# CoPro.net
KiCad netlist of a schematic drawn in EAGLE
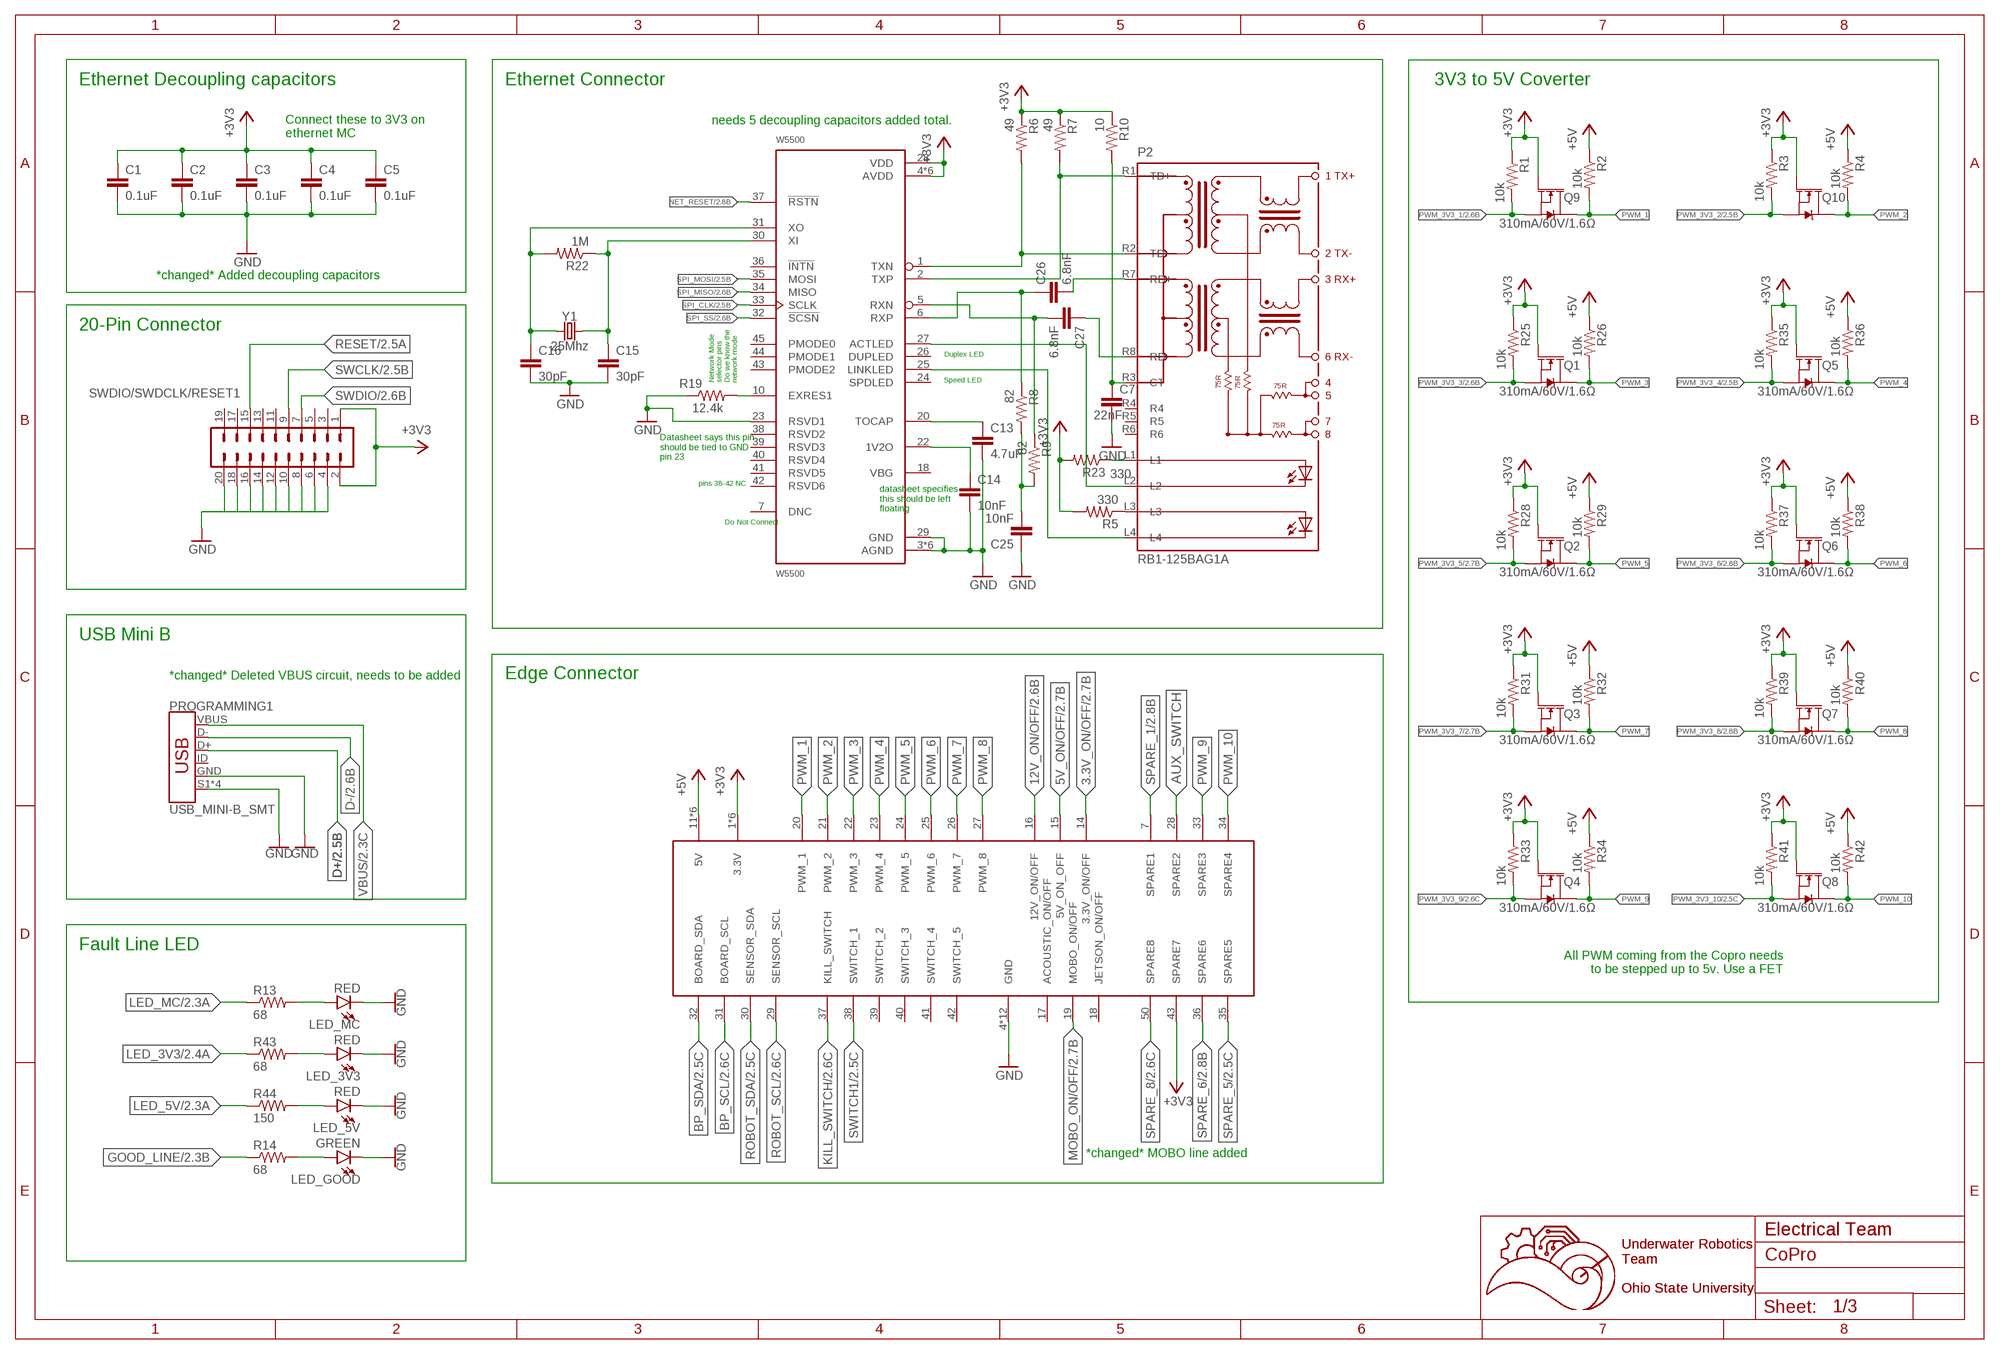
[diagram p0: schematic, sheet 1]
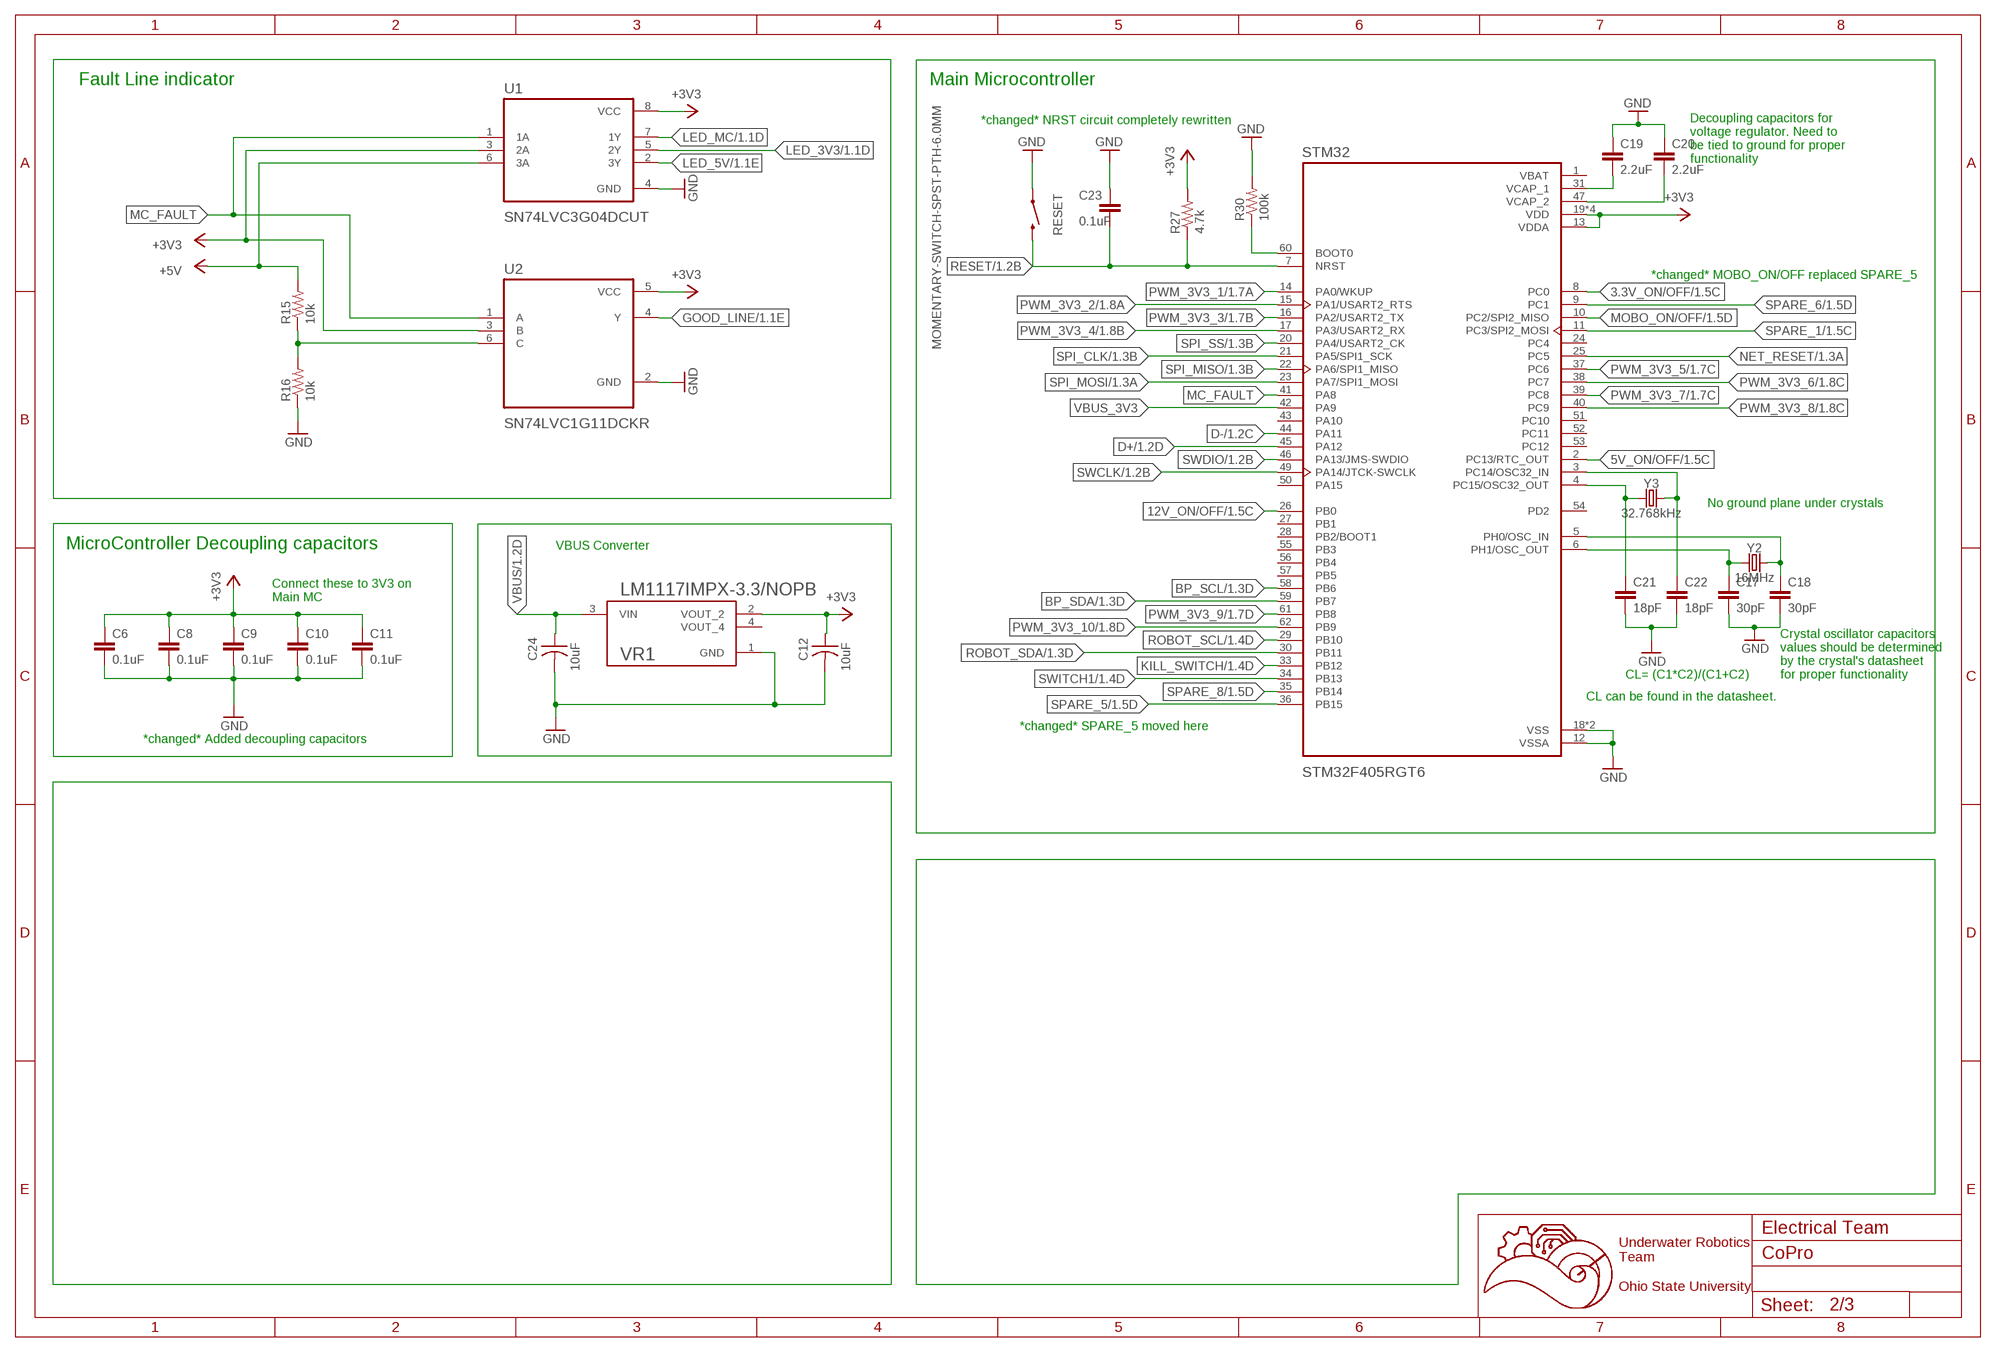
[diagram p1: schematic, sheet 2]
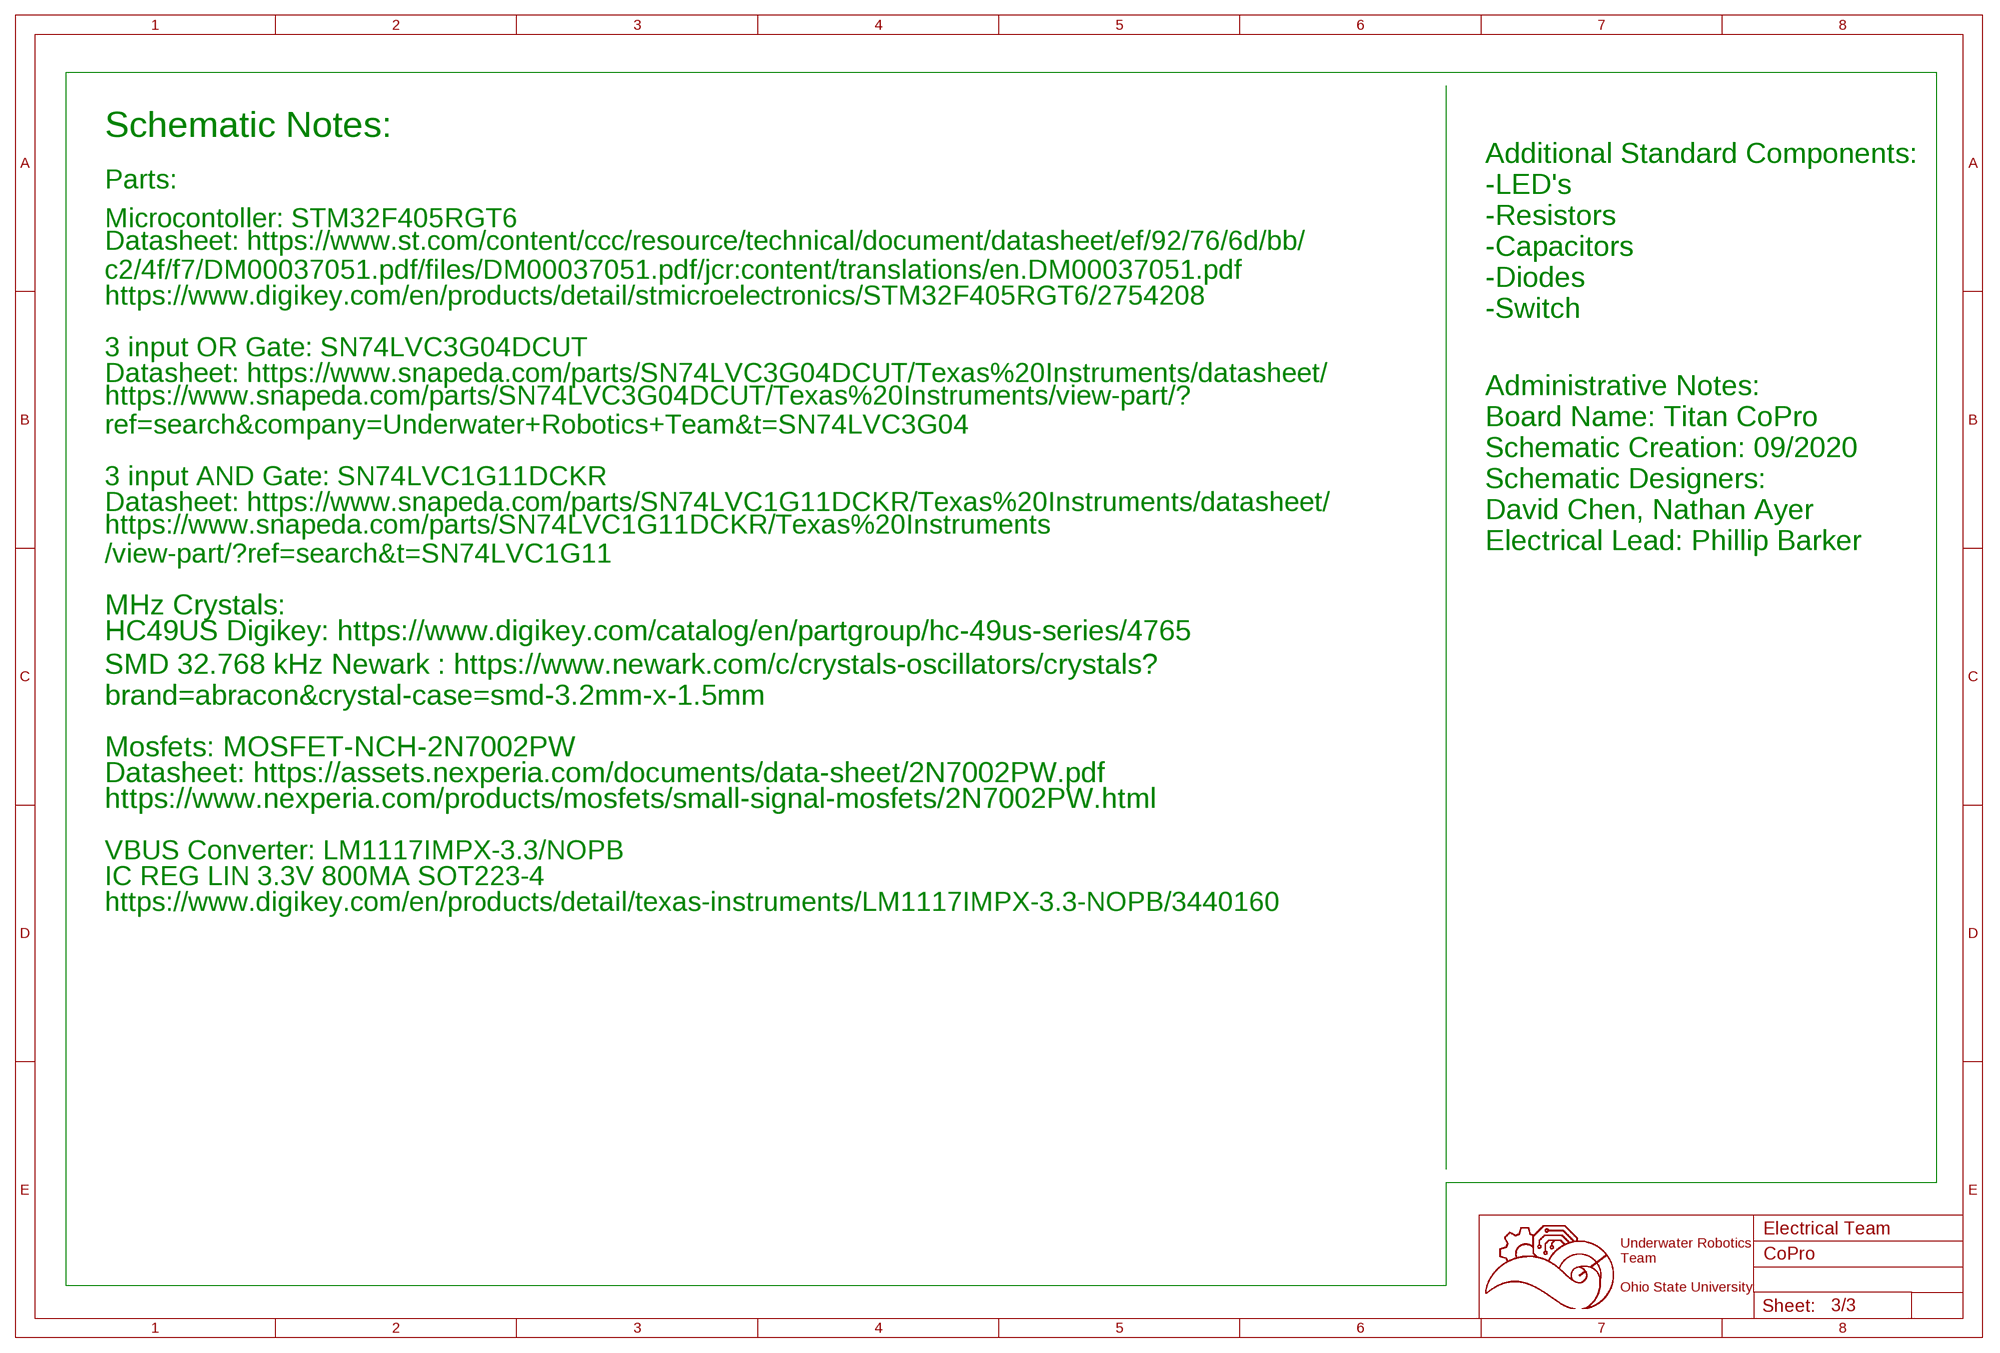
[diagram p2: schematic, sheet 3]

(export (version "E")
  (design (tool "Eeschema 10.0.6"))
  (components
    (comp (ref "C6")
      (value "0.1uF")
      (footprint "eagle-import:C0603")
      (libsource (lib "eagle-import") (part "C-EUC0603"))
    )
    (comp (ref "C8")
      (value "0.1uF")
      (footprint "eagle-import:C0603")
      (libsource (lib "eagle-import") (part "C-EUC0603"))
    )
    (comp (ref "C9")
      (value "0.1uF")
      (footprint "eagle-import:C0603")
      (libsource (lib "eagle-import") (part "C-EUC0603"))
    )
    (comp (ref "C10")
      (value "0.1uF")
      (footprint "eagle-import:C0603")
      (libsource (lib "eagle-import") (part "C-EUC0603"))
    )
    (comp (ref "C11")
      (value "0.1uF")
      (footprint "eagle-import:C0603")
      (libsource (lib "eagle-import") (part "C-EUC0603"))
    )
    (comp (ref "C12")
      (value "10uF")
      (footprint "eagle-import:C0603")
      (libsource (lib "eagle-import") (part "C-USC0603"))
    )
    (comp (ref "C17")
      (value "30pF")
      (footprint "eagle-import:C0603")
      (libsource (lib "eagle-import") (part "C-EUC0603"))
    )
    (comp (ref "C18")
      (value "30pF")
      (footprint "eagle-import:C0603")
      (libsource (lib "eagle-import") (part "C-EUC0603"))
    )
    (comp (ref "C19")
      (value "2.2uF")
      (footprint "eagle-import:C0603")
      (libsource (lib "eagle-import") (part "C-EUC0603"))
    )
    (comp (ref "C20")
      (value "2.2uF")
      (footprint "eagle-import:C0603")
      (libsource (lib "eagle-import") (part "C-EUC0603"))
    )
    (comp (ref "C21")
      (value "18pF")
      (footprint "eagle-import:C0603")
      (libsource (lib "eagle-import") (part "C-EUC0603"))
    )
    (comp (ref "C22")
      (value "18pF")
      (footprint "eagle-import:C0603")
      (libsource (lib "eagle-import") (part "C-EUC0603"))
    )
    (comp (ref "C23")
      (value "0.1uF")
      (footprint "eagle-import:C0603")
      (libsource (lib "eagle-import") (part "C-EUC0603"))
    )
    (comp (ref "C24")
      (value "10uF")
      (footprint "eagle-import:C0603")
      (libsource (lib "eagle-import") (part "C-USC0603"))
    )
    (comp (ref "R15")
      (value "10k")
      (footprint "eagle-import:R0603")
      (libsource (lib "eagle-import") (part "R-US_R0603"))
    )
    (comp (ref "R16")
      (value "10k")
      (footprint "eagle-import:R0603")
      (libsource (lib "eagle-import") (part "R-US_R0603"))
    )
    (comp (ref "R27")
      (value "4.7k")
      (footprint "eagle-import:R0603")
      (libsource (lib "eagle-import") (part "R-US_R0603"))
    )
    (comp (ref "R30")
      (value "100k")
      (footprint "eagle-import:R0603")
      (libsource (lib "eagle-import") (part "R-US_R0603"))
    )
    (comp (ref "RESET")
      (value "MOMENTARY-SWITCH-SPST-PTH-6.0MM")
      (footprint "eagle-import:TACTILE_SWITCH_PTH_6.0MM")
      (libsource (lib "eagle-import") (part "MOMENTARY-SWITCH-SPST-PTH-6.0MM"))
    )
    (comp (ref "STM32")
      (value "STM32F405RGT6")
      (footprint "eagle-import:QFP50P1200X1200X160-64N")
      (fields (field (name "MF") "STMicroelectronics"))
      (libsource (lib "eagle-import") (part "STM32F405RGT6"))
    )
    (comp (ref "U1")
      (value "SN74LVC3G04DCUT")
      (footprint "eagle-import:SOP50P310X90-8N")
      (fields (field (name "MF") "Texas Instruments"))
      (libsource (lib "eagle-import") (part "SN74LVC3G04DCUT"))
    )
    (comp (ref "U2")
      (value "SN74LVC1G11DCKR")
      (footprint "eagle-import:SOT65P210X110-6N")
      (fields (field (name "MF") "Texas Instruments"))
      (libsource (lib "eagle-import") (part "SN74LVC1G11DCKR"))
    )
    (comp (ref "VR1")
      (value "LM1117IMPX-3.3/NOPB")
      (footprint "eagle-import:VREG_LM1117IMPX-3.3_NOPB")
      (fields (field (name "MF") "Texas Instruments"))
      (libsource (lib "eagle-import") (part "LM1117IMPX-3.3/NOPB"))
    )
    (comp (ref "Y2")
      (value "16MHz")
      (footprint "eagle-import:HC49US")
      (libsource (lib "eagle-import") (part "CRYSTAL-16MHZPTH-HC49US"))
    )
    (comp (ref "Y3")
      (value "32.768kHz")
      (footprint "eagle-import:CRYSTAL-SMD-3.2X1.5MM")
      (libsource (lib "eagle-import") (part "CRYSTAL-32.768KHZSMD-3.2X1.5"))
    )
    (comp (ref "C1")
      (value "0.1uF")
      (footprint "eagle-import:C0603")
      (libsource (lib "eagle-import") (part "C-EUC0603"))
    )
    (comp (ref "C2")
      (value "0.1uF")
      (footprint "eagle-import:C0603")
      (libsource (lib "eagle-import") (part "C-EUC0603"))
    )
    (comp (ref "C3")
      (value "0.1uF")
      (footprint "eagle-import:C0603")
      (libsource (lib "eagle-import") (part "C-EUC0603"))
    )
    (comp (ref "C4")
      (value "0.1uF")
      (footprint "eagle-import:C0603")
      (libsource (lib "eagle-import") (part "C-EUC0603"))
    )
    (comp (ref "C5")
      (value "0.1uF")
      (footprint "eagle-import:C0603")
      (libsource (lib "eagle-import") (part "C-EUC0603"))
    )
    (comp (ref "C7")
      (value "22nF")
      (footprint "eagle-import:C0603")
      (libsource (lib "eagle-import") (part "C-EUC0603"))
    )
    (comp (ref "C13")
      (value "4.7uF")
      (footprint "eagle-import:C0603")
      (libsource (lib "eagle-import") (part "C-EUC0603"))
    )
    (comp (ref "C14")
      (value "10nF")
      (footprint "eagle-import:C0603")
      (libsource (lib "eagle-import") (part "C-EUC0603"))
    )
    (comp (ref "C15")
      (value "30pF")
      (footprint "eagle-import:C0603")
      (libsource (lib "eagle-import") (part "C-EUC0603"))
    )
    (comp (ref "C16")
      (value "30pF")
      (footprint "eagle-import:C0603")
      (libsource (lib "eagle-import") (part "C-EUC0603"))
    )
    (comp (ref "C25")
      (value "10nF")
      (footprint "eagle-import:C0603")
      (libsource (lib "eagle-import") (part "C-EUC0603"))
    )
    (comp (ref "C26")
      (value "6.8nF")
      (footprint "eagle-import:C0603")
      (libsource (lib "eagle-import") (part "C-EUC0603"))
    )
    (comp (ref "C27")
      (value "6.8nF")
      (footprint "eagle-import:C0603")
      (libsource (lib "eagle-import") (part "C-EUC0603"))
    )
    (comp (ref "LED_3V3")
      (value "RED")
      (footprint "eagle-import:LED-0603")
      (libsource (lib "eagle-import") (part "LED0603"))
    )
    (comp (ref "LED_5V")
      (value "RED")
      (footprint "eagle-import:LED-0603")
      (libsource (lib "eagle-import") (part "LED0603"))
    )
    (comp (ref "LED_GOOD")
      (value "GREEN")
      (footprint "eagle-import:LED-0603")
      (libsource (lib "eagle-import") (part "LED0603"))
    )
    (comp (ref "LED_MC")
      (value "RED")
      (footprint "eagle-import:LED-0603")
      (libsource (lib "eagle-import") (part "LED0603"))
    )
    (comp (ref "P2")
      (value "RB1-125BAG1A")
      (footprint "eagle-import:WIZNET_RB1-125BAG1A")
      (fields (field (name "MF") "WIZnet"))
      (libsource (lib "eagle-import") (part "RB1-125BAG1A"))
    )
    (comp (ref "PROGRAMMING1")
      (value "USB_MINI-B_SMT")
      (footprint "eagle-import:USB-MINIB")
      (libsource (lib "eagle-import") (part "USB_MINI-B_SMT"))
    )
    (comp (ref "Q1")
      (value "310mA/60V/1.6Ω")
      (footprint "eagle-import:SOT323")
      (libsource (lib "eagle-import") (part "MOSFET-NCH-2N7002PW"))
    )
    (comp (ref "Q2")
      (value "310mA/60V/1.6Ω")
      (footprint "eagle-import:SOT323")
      (libsource (lib "eagle-import") (part "MOSFET-NCH-2N7002PW"))
    )
    (comp (ref "Q3")
      (value "310mA/60V/1.6Ω")
      (footprint "eagle-import:SOT323")
      (libsource (lib "eagle-import") (part "MOSFET-NCH-2N7002PW"))
    )
    (comp (ref "Q4")
      (value "310mA/60V/1.6Ω")
      (footprint "eagle-import:SOT323")
      (libsource (lib "eagle-import") (part "MOSFET-NCH-2N7002PW"))
    )
    (comp (ref "Q5")
      (value "310mA/60V/1.6Ω")
      (footprint "eagle-import:SOT323")
      (libsource (lib "eagle-import") (part "MOSFET-NCH-2N7002PW"))
    )
    (comp (ref "Q6")
      (value "310mA/60V/1.6Ω")
      (footprint "eagle-import:SOT323")
      (libsource (lib "eagle-import") (part "MOSFET-NCH-2N7002PW"))
    )
    (comp (ref "Q7")
      (value "310mA/60V/1.6Ω")
      (footprint "eagle-import:SOT323")
      (libsource (lib "eagle-import") (part "MOSFET-NCH-2N7002PW"))
    )
    (comp (ref "Q8")
      (value "310mA/60V/1.6Ω")
      (footprint "eagle-import:SOT323")
      (libsource (lib "eagle-import") (part "MOSFET-NCH-2N7002PW"))
    )
    (comp (ref "Q9")
      (value "310mA/60V/1.6Ω")
      (footprint "eagle-import:SOT323")
      (libsource (lib "eagle-import") (part "MOSFET-NCH-2N7002PW"))
    )
    (comp (ref "Q10")
      (value "310mA/60V/1.6Ω")
      (footprint "eagle-import:SOT323")
      (libsource (lib "eagle-import") (part "MOSFET-NCH-2N7002PW"))
    )
    (comp (ref "R1")
      (value "10k")
      (footprint "eagle-import:R0603")
      (libsource (lib "eagle-import") (part "R-US_R0603"))
    )
    (comp (ref "R2")
      (value "10k")
      (footprint "eagle-import:R0603")
      (libsource (lib "eagle-import") (part "R-US_R0603"))
    )
    (comp (ref "R3")
      (value "10k")
      (footprint "eagle-import:R0603")
      (libsource (lib "eagle-import") (part "R-US_R0603"))
    )
    (comp (ref "R4")
      (value "10k")
      (footprint "eagle-import:R0603")
      (libsource (lib "eagle-import") (part "R-US_R0603"))
    )
    (comp (ref "R5")
      (value "330")
      (footprint "eagle-import:R0603")
      (libsource (lib "eagle-import") (part "R-US_R0603"))
    )
    (comp (ref "R6")
      (value "49")
      (footprint "eagle-import:R0603")
      (libsource (lib "eagle-import") (part "R-US_R0603"))
    )
    (comp (ref "R7")
      (value "49")
      (footprint "eagle-import:R0603")
      (libsource (lib "eagle-import") (part "R-US_R0603"))
    )
    (comp (ref "R8")
      (value "82")
      (footprint "eagle-import:R0603")
      (libsource (lib "eagle-import") (part "R-US_R0603"))
    )
    (comp (ref "R9")
      (value "82")
      (footprint "eagle-import:R0603")
      (libsource (lib "eagle-import") (part "R-US_R0603"))
    )
    (comp (ref "R10")
      (value "10")
      (footprint "eagle-import:R0603")
      (libsource (lib "eagle-import") (part "R-US_R0603"))
    )
    (comp (ref "R13")
      (value "68")
      (footprint "eagle-import:R0603")
      (libsource (lib "eagle-import") (part "R-US_R0603"))
    )
    (comp (ref "R14")
      (value "68")
      (footprint "eagle-import:R0603")
      (libsource (lib "eagle-import") (part "R-US_R0603"))
    )
    (comp (ref "R19")
      (value "12.4k")
      (footprint "eagle-import:R0603")
      (libsource (lib "eagle-import") (part "R-US_R0603"))
    )
    (comp (ref "R22")
      (value "1M")
      (footprint "eagle-import:R0603")
      (libsource (lib "eagle-import") (part "R-US_R0603"))
    )
    (comp (ref "R23")
      (value "330")
      (footprint "eagle-import:R0603")
      (libsource (lib "eagle-import") (part "R-US_R0603"))
    )
    (comp (ref "R25")
      (value "10k")
      (footprint "eagle-import:R0603")
      (libsource (lib "eagle-import") (part "R-US_R0603"))
    )
    (comp (ref "R26")
      (value "10k")
      (footprint "eagle-import:R0603")
      (libsource (lib "eagle-import") (part "R-US_R0603"))
    )
    (comp (ref "R28")
      (value "10k")
      (footprint "eagle-import:R0603")
      (libsource (lib "eagle-import") (part "R-US_R0603"))
    )
    (comp (ref "R29")
      (value "10k")
      (footprint "eagle-import:R0603")
      (libsource (lib "eagle-import") (part "R-US_R0603"))
    )
    (comp (ref "R31")
      (value "10k")
      (footprint "eagle-import:R0603")
      (libsource (lib "eagle-import") (part "R-US_R0603"))
    )
    (comp (ref "R32")
      (value "10k")
      (footprint "eagle-import:R0603")
      (libsource (lib "eagle-import") (part "R-US_R0603"))
    )
    (comp (ref "R33")
      (value "10k")
      (footprint "eagle-import:R0603")
      (libsource (lib "eagle-import") (part "R-US_R0603"))
    )
    (comp (ref "R34")
      (value "10k")
      (footprint "eagle-import:R0603")
      (libsource (lib "eagle-import") (part "R-US_R0603"))
    )
    (comp (ref "R35")
      (value "10k")
      (footprint "eagle-import:R0603")
      (libsource (lib "eagle-import") (part "R-US_R0603"))
    )
    (comp (ref "R36")
      (value "10k")
      (footprint "eagle-import:R0603")
      (libsource (lib "eagle-import") (part "R-US_R0603"))
    )
    (comp (ref "R37")
      (value "10k")
      (footprint "eagle-import:R0603")
      (libsource (lib "eagle-import") (part "R-US_R0603"))
    )
    (comp (ref "R38")
      (value "10k")
      (footprint "eagle-import:R0603")
      (libsource (lib "eagle-import") (part "R-US_R0603"))
    )
    (comp (ref "R39")
      (value "10k")
      (footprint "eagle-import:R0603")
      (libsource (lib "eagle-import") (part "R-US_R0603"))
    )
    (comp (ref "R40")
      (value "10k")
      (footprint "eagle-import:R0603")
      (libsource (lib "eagle-import") (part "R-US_R0603"))
    )
    (comp (ref "R41")
      (value "10k")
      (footprint "eagle-import:R0603")
      (libsource (lib "eagle-import") (part "R-US_R0603"))
    )
    (comp (ref "R42")
      (value "10k")
      (footprint "eagle-import:R0603")
      (libsource (lib "eagle-import") (part "R-US_R0603"))
    )
    (comp (ref "R43")
      (value "68")
      (footprint "eagle-import:R0603")
      (libsource (lib "eagle-import") (part "R-US_R0603"))
    )
    (comp (ref "R44")
      (value "150")
      (footprint "eagle-import:R0603")
      (libsource (lib "eagle-import") (part "R-US_R0603"))
    )
    (comp (ref "SWDIO/SWDCLK/RESET1")
      (value "CONN_10X2")
      (footprint "eagle-import:2X10")
      (libsource (lib "eagle-import") (part "CONN_10X2"))
    )
    (comp (ref "U$1")
      (value "5530843-EDGE")
      (footprint "eagle-import:5530843-6-BOARDFINGERS")
      (libsource (lib "eagle-import") (part "5530843-EDGE"))
    )
    (comp (ref "W5500")
      (value "W5500")
      (footprint "eagle-import:QFP50P900X900X160-48N")
      (fields (field (name "MF") "WIZnet"))
      (libsource (lib "eagle-import") (part "W5500"))
    )
    (comp (ref "Y1")
      (value "25Mhz")
      (footprint "eagle-import:HC49US")
      (libsource (lib "eagle-import") (part "CRYSTALPTH-HC49US"))
    )
  )
  (nets
    (net (code "1") (name "+3V3") (class "Default")
      (node (ref "C1") (pin "1") (pinfunction "1_1") (pintype "passive"))
      (node (ref "C10") (pin "1") (pinfunction "1_1") (pintype "passive"))
      (node (ref "C11") (pin "1") (pinfunction "1_1") (pintype "passive"))
      (node (ref "C12") (pin "1") (pinfunction "1_1") (pintype "passive"))
      (node (ref "C2") (pin "1") (pinfunction "1_1") (pintype "passive"))
      (node (ref "C3") (pin "1") (pinfunction "1_1") (pintype "passive"))
      (node (ref "C4") (pin "1") (pinfunction "1_1") (pintype "passive"))
      (node (ref "C5") (pin "1") (pinfunction "1_1") (pintype "passive"))
      (node (ref "C6") (pin "1") (pinfunction "1_1") (pintype "passive"))
      (node (ref "C8") (pin "1") (pinfunction "1_1") (pintype "passive"))
      (node (ref "C9") (pin "1") (pinfunction "1_1") (pintype "passive"))
      (node (ref "Q1") (pin "1") (pinfunction "G_1") (pintype "bidirectional"))
      (node (ref "Q10") (pin "1") (pinfunction "G_1") (pintype "bidirectional"))
      (node (ref "Q2") (pin "1") (pinfunction "G_1") (pintype "bidirectional"))
      (node (ref "Q3") (pin "1") (pinfunction "G_1") (pintype "bidirectional"))
      (node (ref "Q4") (pin "1") (pinfunction "G_1") (pintype "bidirectional"))
      (node (ref "Q5") (pin "1") (pinfunction "G_1") (pintype "bidirectional"))
      (node (ref "Q6") (pin "1") (pinfunction "G_1") (pintype "bidirectional"))
      (node (ref "Q7") (pin "1") (pinfunction "G_1") (pintype "bidirectional"))
      (node (ref "Q8") (pin "1") (pinfunction "G_1") (pintype "bidirectional"))
      (node (ref "Q9") (pin "1") (pinfunction "G_1") (pintype "bidirectional"))
      (node (ref "R1") (pin "1") (pinfunction "1_1") (pintype "passive"))
      (node (ref "R10") (pin "1") (pinfunction "1_1") (pintype "passive"))
      (node (ref "R23") (pin "2") (pinfunction "2_2") (pintype "passive"))
      (node (ref "R25") (pin "1") (pinfunction "1_1") (pintype "passive"))
      (node (ref "R27") (pin "2") (pinfunction "2_2") (pintype "passive"))
      (node (ref "R28") (pin "1") (pinfunction "1_1") (pintype "passive"))
      (node (ref "R3") (pin "1") (pinfunction "1_1") (pintype "passive"))
      (node (ref "R31") (pin "1") (pinfunction "1_1") (pintype "passive"))
      (node (ref "R33") (pin "1") (pinfunction "1_1") (pintype "passive"))
      (node (ref "R35") (pin "1") (pinfunction "1_1") (pintype "passive"))
      (node (ref "R37") (pin "1") (pinfunction "1_1") (pintype "passive"))
      (node (ref "R39") (pin "1") (pinfunction "1_1") (pintype "passive"))
      (node (ref "R41") (pin "1") (pinfunction "1_1") (pintype "passive"))
      (node (ref "R5") (pin "2") (pinfunction "2_2") (pintype "passive"))
      (node (ref "R6") (pin "1") (pinfunction "1_1") (pintype "passive"))
      (node (ref "R7") (pin "1") (pinfunction "1_1") (pintype "passive"))
      (node (ref "STM32") (pin "13") (pinfunction "VDDA_13") (pintype "power_in"))
      (node (ref "STM32") (pin "19") (pinfunction "VDD_19") (pintype "power_in"))
      (node (ref "STM32") (pin "32") (pinfunction "VDD_32") (pintype "power_in"))
      (node (ref "STM32") (pin "48") (pinfunction "VDD_48") (pintype "power_in"))
      (node (ref "STM32") (pin "64") (pinfunction "VDD_64") (pintype "power_in"))
      (node (ref "SWDIO/SWDCLK/RESET1") (pin "1") (pinfunction "1_1") (pintype "passive"))
      (node (ref "SWDIO/SWDCLK/RESET1") (pin "2") (pinfunction "2_2") (pintype "passive"))
      (node (ref "U$1") (pin "1") (pinfunction "3.3V_1") (pintype "bidirectional"))
      (node (ref "U$1") (pin "2") (pinfunction "3.3V_2") (pintype "bidirectional"))
      (node (ref "U$1") (pin "3") (pinfunction "3.3V_3") (pintype "bidirectional"))
      (node (ref "U$1") (pin "43") (pinfunction "SPARE7_43") (pintype "bidirectional"))
      (node (ref "U$1") (pin "54") (pinfunction "3.3V_54") (pintype "bidirectional"))
      (node (ref "U$1") (pin "55") (pinfunction "3.3V_55") (pintype "bidirectional"))
      (node (ref "U$1") (pin "56") (pinfunction "3.3V_56") (pintype "bidirectional"))
      (node (ref "U1") (pin "3") (pinfunction "2A_3") (pintype "input"))
      (node (ref "U1") (pin "8") (pinfunction "VCC_8") (pintype "power_in"))
      (node (ref "U2") (pin "3") (pinfunction "B_3") (pintype "input"))
      (node (ref "U2") (pin "5") (pinfunction "VCC_5") (pintype "power_in"))
      (node (ref "VR1") (pin "2") (pinfunction "VOUT_2_2") (pintype "output"))
      (node (ref "W5500") (pin "11") (pinfunction "AVDD_11") (pintype "power_in"))
      (node (ref "W5500") (pin "15") (pinfunction "AVDD_15") (pintype "power_in"))
      (node (ref "W5500") (pin "17") (pinfunction "AVDD_17") (pintype "power_in"))
      (node (ref "W5500") (pin "21") (pinfunction "AVDD_21") (pintype "power_in"))
      (node (ref "W5500") (pin "28") (pinfunction "VDD_28") (pintype "power_in"))
      (node (ref "W5500") (pin "4") (pinfunction "AVDD_4") (pintype "power_in"))
      (node (ref "W5500") (pin "8") (pinfunction "AVDD_8") (pintype "power_in"))
    )
    (net (code "2") (name "+5V") (class "Default")
      (node (ref "R15") (pin "2") (pinfunction "2_2") (pintype "passive"))
      (node (ref "R2") (pin "1") (pinfunction "1_1") (pintype "passive"))
      (node (ref "R26") (pin "1") (pinfunction "1_1") (pintype "passive"))
      (node (ref "R29") (pin "1") (pinfunction "1_1") (pintype "passive"))
      (node (ref "R32") (pin "1") (pinfunction "1_1") (pintype "passive"))
      (node (ref "R34") (pin "1") (pinfunction "1_1") (pintype "passive"))
      (node (ref "R36") (pin "1") (pinfunction "1_1") (pintype "passive"))
      (node (ref "R38") (pin "1") (pinfunction "1_1") (pintype "passive"))
      (node (ref "R4") (pin "1") (pinfunction "1_1") (pintype "passive"))
      (node (ref "R40") (pin "1") (pinfunction "1_1") (pintype "passive"))
      (node (ref "R42") (pin "1") (pinfunction "1_1") (pintype "passive"))
      (node (ref "U$1") (pin "11") (pinfunction "5V_11") (pintype "bidirectional"))
      (node (ref "U$1") (pin "12") (pinfunction "5V_12") (pintype "bidirectional"))
      (node (ref "U$1") (pin "13") (pinfunction "5V_13") (pintype "bidirectional"))
      (node (ref "U$1") (pin "44") (pinfunction "5V_44") (pintype "bidirectional"))
      (node (ref "U$1") (pin "45") (pinfunction "5V_45") (pintype "bidirectional"))
      (node (ref "U$1") (pin "46") (pinfunction "5V_46") (pintype "bidirectional"))
      (node (ref "U1") (pin "6") (pinfunction "3A_6") (pintype "input"))
    )
    (net (code "3") (name "3.3V_ON{slash}OFF") (class "Default")
      (node (ref "STM32") (pin "8") (pinfunction "PC0_8") (pintype "bidirectional"))
      (node (ref "U$1") (pin "14") (pinfunction "3.3V_ON/OFF_14") (pintype "bidirectional"))
    )
    (net (code "4") (name "5V_ON{slash}OFF") (class "Default")
      (node (ref "STM32") (pin "2") (pinfunction "PC13/RTC_OUT_2") (pintype "bidirectional"))
      (node (ref "U$1") (pin "15") (pinfunction "5V_ON_OFF_15") (pintype "bidirectional"))
    )
    (net (code "5") (name "12V_ON{slash}OFF") (class "Default")
      (node (ref "STM32") (pin "26") (pinfunction "PB0_26") (pintype "bidirectional"))
      (node (ref "U$1") (pin "16") (pinfunction "12V_ON/OFF_16") (pintype "bidirectional"))
    )
    (net (code "6") (name "AUX_SWITCH") (class "Default")
      (node (ref "U$1") (pin "28") (pinfunction "SPARE2_28") (pintype "bidirectional"))
    )
    (net (code "7") (name "BP_SCL") (class "Default")
      (node (ref "STM32") (pin "58") (pinfunction "PB6_58") (pintype "bidirectional"))
      (node (ref "U$1") (pin "31") (pinfunction "BOARD_SCL_31") (pintype "bidirectional"))
    )
    (net (code "8") (name "BP_SDA") (class "Default")
      (node (ref "STM32") (pin "59") (pinfunction "PB7_59") (pintype "bidirectional"))
      (node (ref "U$1") (pin "32") (pinfunction "BOARD_SDA_32") (pintype "bidirectional"))
    )
    (net (code "9") (name "D+") (class "Default")
      (node (ref "PROGRAMMING1") (pin "D+") (pinfunction "D+_D+") (pintype "bidirectional"))
      (node (ref "STM32") (pin "45") (pinfunction "PA12_45") (pintype "bidirectional"))
    )
    (net (code "10") (name "D-") (class "Default")
      (node (ref "PROGRAMMING1") (pin "D-") (pinfunction "D-_D-") (pintype "bidirectional"))
      (node (ref "STM32") (pin "44") (pinfunction "PA11_44") (pintype "bidirectional"))
    )
    (net (code "11") (name "GND") (class "Default")
      (node (ref "C1") (pin "2") (pinfunction "2_2") (pintype "passive"))
      (node (ref "C10") (pin "2") (pinfunction "2_2") (pintype "passive"))
      (node (ref "C11") (pin "2") (pinfunction "2_2") (pintype "passive"))
      (node (ref "C12") (pin "2") (pinfunction "2_2") (pintype "passive"))
      (node (ref "C13") (pin "2") (pinfunction "2_2") (pintype "passive"))
      (node (ref "C14") (pin "2") (pinfunction "2_2") (pintype "passive"))
      (node (ref "C15") (pin "2") (pinfunction "2_2") (pintype "passive"))
      (node (ref "C16") (pin "2") (pinfunction "2_2") (pintype "passive"))
      (node (ref "C17") (pin "2") (pinfunction "2_2") (pintype "passive"))
      (node (ref "C18") (pin "2") (pinfunction "2_2") (pintype "passive"))
      (node (ref "C19") (pin "1") (pinfunction "1_1") (pintype "passive"))
      (node (ref "C2") (pin "2") (pinfunction "2_2") (pintype "passive"))
      (node (ref "C20") (pin "1") (pinfunction "1_1") (pintype "passive"))
      (node (ref "C21") (pin "2") (pinfunction "2_2") (pintype "passive"))
      (node (ref "C22") (pin "2") (pinfunction "2_2") (pintype "passive"))
      (node (ref "C23") (pin "1") (pinfunction "1_1") (pintype "passive"))
      (node (ref "C24") (pin "2") (pinfunction "2_2") (pintype "passive"))
      (node (ref "C25") (pin "1") (pinfunction "1_1") (pintype "passive"))
      (node (ref "C3") (pin "2") (pinfunction "2_2") (pintype "passive"))
      (node (ref "C4") (pin "2") (pinfunction "2_2") (pintype "passive"))
      (node (ref "C5") (pin "2") (pinfunction "2_2") (pintype "passive"))
      (node (ref "C6") (pin "2") (pinfunction "2_2") (pintype "passive"))
      (node (ref "C7") (pin "2") (pinfunction "2_2") (pintype "passive"))
      (node (ref "C8") (pin "2") (pinfunction "2_2") (pintype "passive"))
      (node (ref "C9") (pin "2") (pinfunction "2_2") (pintype "passive"))
      (node (ref "LED_3V3") (pin "C") (pinfunction "C_C") (pintype "passive"))
      (node (ref "LED_5V") (pin "C") (pinfunction "C_C") (pintype "passive"))
      (node (ref "LED_GOOD") (pin "C") (pinfunction "C_C") (pintype "passive"))
      (node (ref "LED_MC") (pin "C") (pinfunction "C_C") (pintype "passive"))
      (node (ref "PROGRAMMING1") (pin "GND") (pinfunction "GND_GND") (pintype "power_in"))
      (node (ref "PROGRAMMING1") (pin "S1") (pinfunction "SHIELD_S1") (pintype "bidirectional"))
      (node (ref "PROGRAMMING1") (pin "S2") (pinfunction "SHIELD_S2") (pintype "bidirectional"))
      (node (ref "PROGRAMMING1") (pin "S3") (pinfunction "SHIELD_S3") (pintype "bidirectional"))
      (node (ref "PROGRAMMING1") (pin "S4") (pinfunction "SHIELD_S4") (pintype "bidirectional"))
      (node (ref "R16") (pin "1") (pinfunction "1_1") (pintype "passive"))
      (node (ref "R19") (pin "1") (pinfunction "1_1") (pintype "passive"))
      (node (ref "R30") (pin "2") (pinfunction "2_2") (pintype "passive"))
      (node (ref "RESET") (pin "1") (pinfunction "1_1") (pintype "passive"))
      (node (ref "STM32") (pin "12") (pinfunction "VSSA_12") (pintype "power_in"))
      (node (ref "STM32") (pin "18") (pinfunction "VSS_18") (pintype "power_in"))
      (node (ref "STM32") (pin "63") (pinfunction "VSS_63") (pintype "power_in"))
      (node (ref "SWDIO/SWDCLK/RESET1") (pin "10") (pinfunction "10_10") (pintype "passive"))
      (node (ref "SWDIO/SWDCLK/RESET1") (pin "12") (pinfunction "12_12") (pintype "passive"))
      (node (ref "SWDIO/SWDCLK/RESET1") (pin "14") (pinfunction "14_14") (pintype "passive"))
      (node (ref "SWDIO/SWDCLK/RESET1") (pin "16") (pinfunction "16_16") (pintype "passive"))
      (node (ref "SWDIO/SWDCLK/RESET1") (pin "18") (pinfunction "18_18") (pintype "passive"))
      (node (ref "SWDIO/SWDCLK/RESET1") (pin "20") (pinfunction "20_20") (pintype "passive"))
      (node (ref "SWDIO/SWDCLK/RESET1") (pin "4") (pinfunction "4_4") (pintype "passive"))
      (node (ref "SWDIO/SWDCLK/RESET1") (pin "6") (pinfunction "6_6") (pintype "passive"))
      (node (ref "SWDIO/SWDCLK/RESET1") (pin "8") (pinfunction "8_8") (pintype "passive"))
      (node (ref "U$1") (pin "10") (pinfunction "GND_10") (pintype "bidirectional"))
      (node (ref "U$1") (pin "4") (pinfunction "GND_4") (pintype "bidirectional"))
      (node (ref "U$1") (pin "47") (pinfunction "GND_47") (pintype "bidirectional"))
      (node (ref "U$1") (pin "48") (pinfunction "GND_48") (pintype "bidirectional"))
      (node (ref "U$1") (pin "49") (pinfunction "GND_49") (pintype "bidirectional"))
      (node (ref "U$1") (pin "5") (pinfunction "GND_5") (pintype "bidirectional"))
      (node (ref "U$1") (pin "51") (pinfunction "GND_51") (pintype "bidirectional"))
      (node (ref "U$1") (pin "52") (pinfunction "GND_52") (pintype "bidirectional"))
      (node (ref "U$1") (pin "53") (pinfunction "GND_53") (pintype "bidirectional"))
      (node (ref "U$1") (pin "6") (pinfunction "GND_6") (pintype "bidirectional"))
      (node (ref "U$1") (pin "8") (pinfunction "GND_8") (pintype "bidirectional"))
      (node (ref "U$1") (pin "9") (pinfunction "GND_9") (pintype "bidirectional"))
      (node (ref "U1") (pin "4") (pinfunction "GND_4") (pintype "power_in"))
      (node (ref "U2") (pin "2") (pinfunction "GND_2") (pintype "power_in"))
      (node (ref "VR1") (pin "1") (pinfunction "GND_1") (pintype "power_in"))
      (node (ref "W5500") (pin "14") (pinfunction "AGND_14") (pintype "power_in"))
      (node (ref "W5500") (pin "16") (pinfunction "AGND_16") (pintype "power_in"))
      (node (ref "W5500") (pin "19") (pinfunction "AGND_19") (pintype "power_in"))
      (node (ref "W5500") (pin "23") (pinfunction "RSVD1_23") (pintype "input"))
      (node (ref "W5500") (pin "29") (pinfunction "GND_29") (pintype "passive"))
      (node (ref "W5500") (pin "3") (pinfunction "AGND_3") (pintype "power_in"))
      (node (ref "W5500") (pin "48") (pinfunction "AGND_48") (pintype "power_in"))
      (node (ref "W5500") (pin "9") (pinfunction "AGND_9") (pintype "power_in"))
    )
    (net (code "12") (name "GOOD_LINE") (class "Default")
      (node (ref "R14") (pin "1") (pinfunction "1_1") (pintype "passive"))
      (node (ref "U2") (pin "4") (pinfunction "Y_4") (pintype "output"))
    )
    (net (code "13") (name "KILL_SWITCH") (class "Default")
      (node (ref "STM32") (pin "33") (pinfunction "PB12_33") (pintype "bidirectional"))
      (node (ref "U$1") (pin "37") (pinfunction "KILL_SWITCH_37") (pintype "output"))
    )
    (net (code "14") (name "LED_3V3") (class "Default")
      (node (ref "R43") (pin "1") (pinfunction "1_1") (pintype "passive"))
      (node (ref "U1") (pin "5") (pinfunction "2Y_5") (pintype "output"))
    )
    (net (code "15") (name "LED_5V") (class "Default")
      (node (ref "R44") (pin "1") (pinfunction "1_1") (pintype "passive"))
      (node (ref "U1") (pin "2") (pinfunction "3Y_2") (pintype "output"))
    )
    (net (code "16") (name "LED_MC") (class "Default")
      (node (ref "R13") (pin "1") (pinfunction "1_1") (pintype "passive"))
      (node (ref "U1") (pin "7") (pinfunction "1Y_7") (pintype "output"))
    )
    (net (code "17") (name "MC_FAULT") (class "Default")
      (node (ref "STM32") (pin "41") (pinfunction "PA8_41") (pintype "bidirectional"))
      (node (ref "U1") (pin "1") (pinfunction "1A_1") (pintype "input"))
      (node (ref "U2") (pin "1") (pinfunction "A_1") (pintype "input"))
    )
    (net (code "18") (name "MOBO_ON{slash}OFF") (class "Default")
      (node (ref "STM32") (pin "10") (pinfunction "PC2/SPI2_MISO_10") (pintype "bidirectional"))
      (node (ref "U$1") (pin "19") (pinfunction "MOBO_ON/OFF_19") (pintype "bidirectional"))
    )
    (net (code "19") (name "NET_RESET") (class "Default")
      (node (ref "STM32") (pin "25") (pinfunction "PC5_25") (pintype "bidirectional"))
      (node (ref "W5500") (pin "37") (pinfunction "~{RSTN}_37") (pintype "input"))
    )
    (net (code "20") (name "Net-(C25-Pad2)") (class "Default")
      (node (ref "C25") (pin "2") (pinfunction "2_2") (pintype "passive"))
      (node (ref "R8") (pin "2") (pinfunction "2_2") (pintype "passive"))
      (node (ref "R9") (pin "2") (pinfunction "2_2") (pintype "passive"))
    )
    (net (code "21") (name "Net-(LED_3V3-PadA)") (class "Default")
      (node (ref "LED_3V3") (pin "A") (pinfunction "A_A") (pintype "passive"))
      (node (ref "R43") (pin "2") (pinfunction "2_2") (pintype "passive"))
    )
    (net (code "22") (name "Net-(LED_5V-PadA)") (class "Default")
      (node (ref "LED_5V") (pin "A") (pinfunction "A_A") (pintype "passive"))
      (node (ref "R44") (pin "2") (pinfunction "2_2") (pintype "passive"))
    )
    (net (code "23") (name "Net-(LED_GOOD-PadA)") (class "Default")
      (node (ref "LED_GOOD") (pin "A") (pinfunction "A_A") (pintype "passive"))
      (node (ref "R14") (pin "2") (pinfunction "2_2") (pintype "passive"))
    )
    (net (code "24") (name "Net-(LED_MC-PadA)") (class "Default")
      (node (ref "LED_MC") (pin "A") (pinfunction "A_A") (pintype "passive"))
      (node (ref "R13") (pin "2") (pinfunction "2_2") (pintype "passive"))
    )
    (net (code "25") (name "Net-(P2-CT)") (class "Default")
      (node (ref "C7") (pin "1") (pinfunction "1_1") (pintype "passive"))
      (node (ref "P2") (pin "R3") (pinfunction "CT_R3") (pintype "input"))
      (node (ref "R10") (pin "2") (pinfunction "2_2") (pintype "passive"))
    )
    (net (code "26") (name "Net-(P2-PadL1)") (class "Default")
      (node (ref "P2") (pin "L1") (pinfunction "L1_L1") (pintype "passive"))
      (node (ref "R23") (pin "1") (pinfunction "1_1") (pintype "passive"))
    )
    (net (code "27") (name "Net-(P2-PadL3)") (class "Default")
      (node (ref "P2") (pin "L3") (pinfunction "L3_L3") (pintype "passive"))
      (node (ref "R5") (pin "1") (pinfunction "1_1") (pintype "passive"))
    )
    (net (code "28") (name "Net-(P2-RD+)") (class "Default")
      (node (ref "C26") (pin "2") (pinfunction "2_2") (pintype "passive"))
      (node (ref "P2") (pin "R7") (pinfunction "RD+_R7") (pintype "input"))
    )
    (net (code "29") (name "Net-(P2-RD-)") (class "Default")
      (node (ref "C27") (pin "1") (pinfunction "1_1") (pintype "passive"))
      (node (ref "P2") (pin "R8") (pinfunction "RD-_R8") (pintype "input"))
    )
    (net (code "30") (name "Net-(P2-TD+)") (class "Default")
      (node (ref "P2") (pin "R1") (pinfunction "TD+_R1") (pintype "input"))
      (node (ref "R7") (pin "2") (pinfunction "2_2") (pintype "passive"))
      (node (ref "W5500") (pin "2") (pinfunction "TXP_2") (pintype "output"))
    )
    (net (code "31") (name "Net-(P2-TD-)") (class "Default")
      (node (ref "P2") (pin "R2") (pinfunction "TD-_R2") (pintype "input"))
      (node (ref "R6") (pin "2") (pinfunction "2_2") (pintype "passive"))
      (node (ref "W5500") (pin "1") (pinfunction "TXN_1") (pintype "output"))
    )
    (net (code "32") (name "Net-(STM32-BOOT0)") (class "Default")
      (node (ref "R30") (pin "1") (pinfunction "1_1") (pintype "passive"))
      (node (ref "STM32") (pin "60") (pinfunction "BOOT0_60") (pintype "bidirectional"))
    )
    (net (code "33") (name "Net-(STM32-PC14{slash}OSC32_IN)") (class "Default")
      (node (ref "C22") (pin "1") (pinfunction "1_1") (pintype "passive"))
      (node (ref "STM32") (pin "3") (pinfunction "PC14/OSC32_IN_3") (pintype "bidirectional"))
      (node (ref "Y3") (pin "P$2") (pinfunction "2_P$2") (pintype "passive"))
    )
    (net (code "34") (name "Net-(STM32-PC15{slash}OSC32_OUT)") (class "Default")
      (node (ref "C21") (pin "1") (pinfunction "1_1") (pintype "passive"))
      (node (ref "STM32") (pin "4") (pinfunction "PC15/OSC32_OUT_4") (pintype "bidirectional"))
      (node (ref "Y3") (pin "P$1") (pinfunction "1_P$1") (pintype "passive"))
    )
    (net (code "35") (name "Net-(STM32-PH0{slash}OSC_IN)") (class "Default")
      (node (ref "C18") (pin "1") (pinfunction "1_1") (pintype "passive"))
      (node (ref "STM32") (pin "5") (pinfunction "PH0/OSC_IN_5") (pintype "bidirectional"))
      (node (ref "Y2") (pin "2") (pinfunction "2_2") (pintype "passive"))
    )
    (net (code "36") (name "Net-(STM32-PH1{slash}OSC_OUT)") (class "Default")
      (node (ref "C17") (pin "1") (pinfunction "1_1") (pintype "passive"))
      (node (ref "STM32") (pin "6") (pinfunction "PH1/OSC_OUT_6") (pintype "bidirectional"))
      (node (ref "Y2") (pin "1") (pinfunction "1_1") (pintype "passive"))
    )
    (net (code "37") (name "Net-(STM32-VCAP_1)") (class "Default")
      (node (ref "C19") (pin "2") (pinfunction "2_2") (pintype "passive"))
      (node (ref "STM32") (pin "31") (pinfunction "VCAP_1_31") (pintype "power_in"))
    )
    (net (code "38") (name "Net-(STM32-VCAP_2)") (class "Default")
      (node (ref "C20") (pin "2") (pinfunction "2_2") (pintype "passive"))
      (node (ref "STM32") (pin "47") (pinfunction "VCAP_2_47") (pintype "power_in"))
    )
    (net (code "39") (name "Net-(U2-C)") (class "Default")
      (node (ref "R15") (pin "1") (pinfunction "1_1") (pintype "passive"))
      (node (ref "R16") (pin "2") (pinfunction "2_2") (pintype "passive"))
      (node (ref "U2") (pin "6") (pinfunction "C_6") (pintype "input"))
    )
    (net (code "40") (name "Net-(W5500-1V2O)") (class "Default")
      (node (ref "C14") (pin "1") (pinfunction "1_1") (pintype "passive"))
      (node (ref "W5500") (pin "22") (pinfunction "1V2O_22") (pintype "output"))
    )
    (net (code "41") (name "Net-(W5500-ACTLED)") (class "Default")
      (node (ref "P2") (pin "L2") (pinfunction "L2_L2") (pintype "passive"))
      (node (ref "W5500") (pin "27") (pinfunction "ACTLED_27") (pintype "output"))
    )
    (net (code "42") (name "Net-(W5500-EXRES1)") (class "Default")
      (node (ref "R19") (pin "2") (pinfunction "2_2") (pintype "passive"))
      (node (ref "W5500") (pin "10") (pinfunction "EXRES1_10") (pintype "bidirectional"))
    )
    (net (code "43") (name "Net-(W5500-LINKLED)") (class "Default")
      (node (ref "P2") (pin "L4") (pinfunction "L4_L4") (pintype "passive"))
      (node (ref "W5500") (pin "25") (pinfunction "LINKLED_25") (pintype "output"))
    )
    (net (code "44") (name "Net-(W5500-RXN)") (class "Default")
      (node (ref "C27") (pin "2") (pinfunction "2_2") (pintype "passive"))
      (node (ref "R9") (pin "1") (pinfunction "1_1") (pintype "passive"))
      (node (ref "W5500") (pin "5") (pinfunction "RXN_5") (pintype "input"))
    )
    (net (code "45") (name "Net-(W5500-RXP)") (class "Default")
      (node (ref "C26") (pin "1") (pinfunction "1_1") (pintype "passive"))
      (node (ref "R8") (pin "1") (pinfunction "1_1") (pintype "passive"))
      (node (ref "W5500") (pin "6") (pinfunction "RXP_6") (pintype "input"))
    )
    (net (code "46") (name "Net-(W5500-TOCAP)") (class "Default")
      (node (ref "C13") (pin "1") (pinfunction "1_1") (pintype "passive"))
      (node (ref "W5500") (pin "20") (pinfunction "TOCAP_20") (pintype "output"))
    )
    (net (code "47") (name "Net-(W5500-XI)") (class "Default")
      (node (ref "C15") (pin "1") (pinfunction "1_1") (pintype "passive"))
      (node (ref "R22") (pin "1") (pinfunction "1_1") (pintype "passive"))
      (node (ref "W5500") (pin "30") (pinfunction "XI_30") (pintype "input"))
      (node (ref "Y1") (pin "2") (pinfunction "2_2") (pintype "passive"))
    )
    (net (code "48") (name "Net-(W5500-XO)") (class "Default")
      (node (ref "C16") (pin "1") (pinfunction "1_1") (pintype "passive"))
      (node (ref "R22") (pin "2") (pinfunction "2_2") (pintype "passive"))
      (node (ref "W5500") (pin "31") (pinfunction "XO_31") (pintype "output"))
      (node (ref "Y1") (pin "1") (pinfunction "1_1") (pintype "passive"))
    )
    (net (code "49") (name "PWM_1") (class "Default")
      (node (ref "Q9") (pin "3") (pinfunction "D_3") (pintype "bidirectional"))
      (node (ref "R2") (pin "2") (pinfunction "2_2") (pintype "passive"))
      (node (ref "U$1") (pin "20") (pinfunction "PWM_1_20") (pintype "bidirectional"))
    )
    (net (code "50") (name "PWM_2") (class "Default")
      (node (ref "Q10") (pin "3") (pinfunction "D_3") (pintype "bidirectional"))
      (node (ref "R4") (pin "2") (pinfunction "2_2") (pintype "passive"))
      (node (ref "U$1") (pin "21") (pinfunction "PWM_2_21") (pintype "bidirectional"))
    )
    (net (code "51") (name "PWM_3") (class "Default")
      (node (ref "Q1") (pin "3") (pinfunction "D_3") (pintype "bidirectional"))
      (node (ref "R26") (pin "2") (pinfunction "2_2") (pintype "passive"))
      (node (ref "U$1") (pin "22") (pinfunction "PWM_3_22") (pintype "bidirectional"))
    )
    (net (code "52") (name "PWM_3V3_1") (class "Default")
      (node (ref "Q9") (pin "2") (pinfunction "S_2") (pintype "bidirectional"))
      (node (ref "R1") (pin "2") (pinfunction "2_2") (pintype "passive"))
      (node (ref "STM32") (pin "14") (pinfunction "PA0/WKUP_14") (pintype "bidirectional"))
    )
    (net (code "53") (name "PWM_3V3_2") (class "Default")
      (node (ref "Q10") (pin "2") (pinfunction "S_2") (pintype "bidirectional"))
      (node (ref "R3") (pin "2") (pinfunction "2_2") (pintype "passive"))
      (node (ref "STM32") (pin "15") (pinfunction "PA1/USART2_RTS_15") (pintype "bidirectional"))
    )
    (net (code "54") (name "PWM_3V3_3") (class "Default")
      (node (ref "Q1") (pin "2") (pinfunction "S_2") (pintype "bidirectional"))
      (node (ref "R25") (pin "2") (pinfunction "2_2") (pintype "passive"))
      (node (ref "STM32") (pin "16") (pinfunction "PA2/USART2_TX_16") (pintype "bidirectional"))
    )
    (net (code "55") (name "PWM_3V3_4") (class "Default")
      (node (ref "Q5") (pin "2") (pinfunction "S_2") (pintype "bidirectional"))
      (node (ref "R35") (pin "2") (pinfunction "2_2") (pintype "passive"))
      (node (ref "STM32") (pin "17") (pinfunction "PA3/USART2_RX_17") (pintype "bidirectional"))
    )
    (net (code "56") (name "PWM_3V3_5") (class "Default")
      (node (ref "Q2") (pin "2") (pinfunction "S_2") (pintype "bidirectional"))
      (node (ref "R28") (pin "2") (pinfunction "2_2") (pintype "passive"))
      (node (ref "STM32") (pin "37") (pinfunction "PC6_37") (pintype "bidirectional"))
    )
    (net (code "57") (name "PWM_3V3_6") (class "Default")
      (node (ref "Q6") (pin "2") (pinfunction "S_2") (pintype "bidirectional"))
      (node (ref "R37") (pin "2") (pinfunction "2_2") (pintype "passive"))
      (node (ref "STM32") (pin "38") (pinfunction "PC7_38") (pintype "bidirectional"))
    )
    (net (code "58") (name "PWM_3V3_7") (class "Default")
      (node (ref "Q3") (pin "2") (pinfunction "S_2") (pintype "bidirectional"))
      (node (ref "R31") (pin "2") (pinfunction "2_2") (pintype "passive"))
      (node (ref "STM32") (pin "39") (pinfunction "PC8_39") (pintype "bidirectional"))
    )
    (net (code "59") (name "PWM_3V3_8") (class "Default")
      (node (ref "Q7") (pin "2") (pinfunction "S_2") (pintype "bidirectional"))
      (node (ref "R39") (pin "2") (pinfunction "2_2") (pintype "passive"))
      (node (ref "STM32") (pin "40") (pinfunction "PC9_40") (pintype "bidirectional"))
    )
    (net (code "60") (name "PWM_3V3_9") (class "Default")
      (node (ref "Q4") (pin "2") (pinfunction "S_2") (pintype "bidirectional"))
      (node (ref "R33") (pin "2") (pinfunction "2_2") (pintype "passive"))
      (node (ref "STM32") (pin "61") (pinfunction "PB8_61") (pintype "bidirectional"))
    )
    (net (code "61") (name "PWM_3V3_10") (class "Default")
      (node (ref "Q8") (pin "2") (pinfunction "S_2") (pintype "bidirectional"))
      (node (ref "R41") (pin "2") (pinfunction "2_2") (pintype "passive"))
      (node (ref "STM32") (pin "62") (pinfunction "PB9_62") (pintype "bidirectional"))
    )
    (net (code "62") (name "PWM_4") (class "Default")
      (node (ref "Q5") (pin "3") (pinfunction "D_3") (pintype "bidirectional"))
      (node (ref "R36") (pin "2") (pinfunction "2_2") (pintype "passive"))
      (node (ref "U$1") (pin "23") (pinfunction "PWM_4_23") (pintype "bidirectional"))
    )
    (net (code "63") (name "PWM_5") (class "Default")
      (node (ref "Q2") (pin "3") (pinfunction "D_3") (pintype "bidirectional"))
      (node (ref "R29") (pin "2") (pinfunction "2_2") (pintype "passive"))
      (node (ref "U$1") (pin "24") (pinfunction "PWM_5_24") (pintype "bidirectional"))
    )
    (net (code "64") (name "PWM_6") (class "Default")
      (node (ref "Q6") (pin "3") (pinfunction "D_3") (pintype "bidirectional"))
      (node (ref "R38") (pin "2") (pinfunction "2_2") (pintype "passive"))
      (node (ref "U$1") (pin "25") (pinfunction "PWM_6_25") (pintype "bidirectional"))
    )
    (net (code "65") (name "PWM_7") (class "Default")
      (node (ref "Q3") (pin "3") (pinfunction "D_3") (pintype "bidirectional"))
      (node (ref "R32") (pin "2") (pinfunction "2_2") (pintype "passive"))
      (node (ref "U$1") (pin "26") (pinfunction "PWM_7_26") (pintype "bidirectional"))
    )
    (net (code "66") (name "PWM_8") (class "Default")
      (node (ref "Q7") (pin "3") (pinfunction "D_3") (pintype "bidirectional"))
      (node (ref "R40") (pin "2") (pinfunction "2_2") (pintype "passive"))
      (node (ref "U$1") (pin "27") (pinfunction "PWM_8_27") (pintype "bidirectional"))
    )
    (net (code "67") (name "PWM_9") (class "Default")
      (node (ref "Q4") (pin "3") (pinfunction "D_3") (pintype "bidirectional"))
      (node (ref "R34") (pin "2") (pinfunction "2_2") (pintype "passive"))
      (node (ref "U$1") (pin "33") (pinfunction "SPARE3_33") (pintype "bidirectional"))
    )
    (net (code "68") (name "PWM_10") (class "Default")
      (node (ref "Q8") (pin "3") (pinfunction "D_3") (pintype "bidirectional"))
      (node (ref "R42") (pin "2") (pinfunction "2_2") (pintype "passive"))
      (node (ref "U$1") (pin "34") (pinfunction "SPARE4_34") (pintype "bidirectional"))
    )
    (net (code "69") (name "RESET") (class "Default")
      (node (ref "C23") (pin "2") (pinfunction "2_2") (pintype "passive"))
      (node (ref "R27") (pin "1") (pinfunction "1_1") (pintype "passive"))
      (node (ref "RESET") (pin "3") (pinfunction "2_3") (pintype "passive"))
      (node (ref "STM32") (pin "7") (pinfunction "NRST_7") (pintype "bidirectional"))
      (node (ref "SWDIO/SWDCLK/RESET1") (pin "15") (pinfunction "15_15") (pintype "passive"))
    )
    (net (code "70") (name "ROBOT_SCL") (class "Default")
      (node (ref "STM32") (pin "29") (pinfunction "PB10_29") (pintype "bidirectional"))
      (node (ref "U$1") (pin "29") (pinfunction "SENSOR_SCL_29") (pintype "bidirectional"))
    )
    (net (code "71") (name "ROBOT_SDA") (class "Default")
      (node (ref "STM32") (pin "30") (pinfunction "PB11_30") (pintype "bidirectional"))
      (node (ref "U$1") (pin "30") (pinfunction "SENSOR_SDA_30") (pintype "bidirectional"))
    )
    (net (code "72") (name "SPARE_1") (class "Default")
      (node (ref "STM32") (pin "11") (pinfunction "PC3/SPI2_MOSI_11") (pintype "bidirectional"))
      (node (ref "U$1") (pin "7") (pinfunction "SPARE1_7") (pintype "bidirectional"))
    )
    (net (code "73") (name "SPARE_5") (class "Default")
      (node (ref "STM32") (pin "36") (pinfunction "PB15_36") (pintype "bidirectional"))
      (node (ref "U$1") (pin "35") (pinfunction "SPARE5_35") (pintype "bidirectional"))
    )
    (net (code "74") (name "SPARE_6") (class "Default")
      (node (ref "STM32") (pin "9") (pinfunction "PC1_9") (pintype "bidirectional"))
      (node (ref "U$1") (pin "36") (pinfunction "SPARE6_36") (pintype "bidirectional"))
    )
    (net (code "75") (name "SPARE_8") (class "Default")
      (node (ref "STM32") (pin "35") (pinfunction "PB14_35") (pintype "bidirectional"))
      (node (ref "U$1") (pin "50") (pinfunction "SPARE8_50") (pintype "bidirectional"))
    )
    (net (code "76") (name "SPI_CLK") (class "Default")
      (node (ref "STM32") (pin "21") (pinfunction "PA5/SPI1_SCK_21") (pintype "bidirectional"))
      (node (ref "W5500") (pin "33") (pinfunction "SCLK_33") (pintype "input"))
    )
    (net (code "77") (name "SPI_MISO") (class "Default")
      (node (ref "STM32") (pin "22") (pinfunction "PA6/SPI1_MISO_22") (pintype "bidirectional"))
      (node (ref "W5500") (pin "34") (pinfunction "MISO_34") (pintype "output"))
    )
    (net (code "78") (name "SPI_MOSI") (class "Default")
      (node (ref "STM32") (pin "23") (pinfunction "PA7/SPI1_MOSI_23") (pintype "bidirectional"))
      (node (ref "W5500") (pin "35") (pinfunction "MOSI_35") (pintype "input"))
    )
    (net (code "79") (name "SPI_SS") (class "Default")
      (node (ref "STM32") (pin "20") (pinfunction "PA4/USART2_CK_20") (pintype "bidirectional"))
      (node (ref "W5500") (pin "32") (pinfunction "~{SCSN}_32") (pintype "input"))
    )
    (net (code "80") (name "SWCLK") (class "Default")
      (node (ref "STM32") (pin "49") (pinfunction "PA14/JTCK-SWCLK_49") (pintype "bidirectional"))
      (node (ref "SWDIO/SWDCLK/RESET1") (pin "9") (pinfunction "9_9") (pintype "passive"))
    )
    (net (code "81") (name "SWDIO") (class "Default")
      (node (ref "STM32") (pin "46") (pinfunction "PA13/JMS-SWDIO_46") (pintype "bidirectional"))
      (node (ref "SWDIO/SWDCLK/RESET1") (pin "7") (pinfunction "7_7") (pintype "passive"))
    )
    (net (code "82") (name "SWITCH1") (class "Default")
      (node (ref "STM32") (pin "34") (pinfunction "PB13_34") (pintype "bidirectional"))
      (node (ref "U$1") (pin "38") (pinfunction "SWITCH_1_38") (pintype "output"))
    )
    (net (code "83") (name "VBAT") (class "Default")
      (node (ref "STM32") (pin "1") (pinfunction "VBAT_1") (pintype "power_in"))
    )
    (net (code "84") (name "VBUS") (class "Default")
      (node (ref "C24") (pin "1") (pinfunction "1_1") (pintype "passive"))
      (node (ref "PROGRAMMING1") (pin "VBUS") (pinfunction "VBUS_VBUS") (pintype "power_in"))
      (node (ref "VR1") (pin "3") (pinfunction "VIN_3") (pintype "input"))
    )
    (net (code "85") (name "VBUS_3V3") (class "Default")
      (node (ref "STM32") (pin "42") (pinfunction "PA9_42") (pintype "bidirectional"))
    )
    (net (code "86") (name "unconnected-(P2-PadR4)") (class "Default")
      (node (ref "P2") (pin "R4") (pinfunction "R4_R4") (pintype "input"))
    )
    (net (code "87") (name "unconnected-(P2-PadR5)") (class "Default")
      (node (ref "P2") (pin "R5") (pinfunction "R5_R5") (pintype "input"))
    )
    (net (code "88") (name "unconnected-(P2-PadR6)") (class "Default")
      (node (ref "P2") (pin "R6") (pinfunction "R6_R6") (pintype "input"))
    )
    (net (code "89") (name "unconnected-(PROGRAMMING1-PadID)") (class "Default")
      (node (ref "PROGRAMMING1") (pin "ID") (pinfunction "ID_ID") (pintype "bidirectional"))
    )
    (net (code "90") (name "unconnected-(STM32-PA10-Pad43)") (class "Default")
      (node (ref "STM32") (pin "43") (pinfunction "PA10_43") (pintype "bidirectional"))
    )
    (net (code "91") (name "unconnected-(STM32-PA15-Pad50)") (class "Default")
      (node (ref "STM32") (pin "50") (pinfunction "PA15_50") (pintype "bidirectional"))
    )
    (net (code "92") (name "unconnected-(STM32-PB1-Pad27)") (class "Default")
      (node (ref "STM32") (pin "27") (pinfunction "PB1_27") (pintype "bidirectional"))
    )
    (net (code "93") (name "unconnected-(STM32-PB2{slash}BOOT1-Pad28)") (class "Default")
      (node (ref "STM32") (pin "28") (pinfunction "PB2/BOOT1_28") (pintype "bidirectional"))
    )
    (net (code "94") (name "unconnected-(STM32-PB3-Pad55)") (class "Default")
      (node (ref "STM32") (pin "55") (pinfunction "PB3_55") (pintype "bidirectional"))
    )
    (net (code "95") (name "unconnected-(STM32-PB4-Pad56)") (class "Default")
      (node (ref "STM32") (pin "56") (pinfunction "PB4_56") (pintype "bidirectional"))
    )
    (net (code "96") (name "unconnected-(STM32-PB5-Pad57)") (class "Default")
      (node (ref "STM32") (pin "57") (pinfunction "PB5_57") (pintype "bidirectional"))
    )
    (net (code "97") (name "unconnected-(STM32-PC4-Pad24)") (class "Default")
      (node (ref "STM32") (pin "24") (pinfunction "PC4_24") (pintype "bidirectional"))
    )
    (net (code "98") (name "unconnected-(STM32-PC10-Pad51)") (class "Default")
      (node (ref "STM32") (pin "51") (pinfunction "PC10_51") (pintype "bidirectional"))
    )
    (net (code "99") (name "unconnected-(STM32-PC11-Pad52)") (class "Default")
      (node (ref "STM32") (pin "52") (pinfunction "PC11_52") (pintype "bidirectional"))
    )
    (net (code "100") (name "unconnected-(STM32-PC12-Pad53)") (class "Default")
      (node (ref "STM32") (pin "53") (pinfunction "PC12_53") (pintype "bidirectional"))
    )
    (net (code "101") (name "unconnected-(STM32-PD2-Pad54)") (class "Default")
      (node (ref "STM32") (pin "54") (pinfunction "PD2_54") (pintype "bidirectional"))
    )
    (net (code "102") (name "unconnected-(SWDIO/SWDCLK/RESET1-Pad3)") (class "Default")
      (node (ref "SWDIO/SWDCLK/RESET1") (pin "3") (pinfunction "3_3") (pintype "passive"))
    )
    (net (code "103") (name "unconnected-(SWDIO/SWDCLK/RESET1-Pad5)") (class "Default")
      (node (ref "SWDIO/SWDCLK/RESET1") (pin "5") (pinfunction "5_5") (pintype "passive"))
    )
    (net (code "104") (name "unconnected-(SWDIO/SWDCLK/RESET1-Pad11)") (class "Default")
      (node (ref "SWDIO/SWDCLK/RESET1") (pin "11") (pinfunction "11_11") (pintype "passive"))
    )
    (net (code "105") (name "unconnected-(SWDIO/SWDCLK/RESET1-Pad13)") (class "Default")
      (node (ref "SWDIO/SWDCLK/RESET1") (pin "13") (pinfunction "13_13") (pintype "passive"))
    )
    (net (code "106") (name "unconnected-(SWDIO/SWDCLK/RESET1-Pad17)") (class "Default")
      (node (ref "SWDIO/SWDCLK/RESET1") (pin "17") (pinfunction "17_17") (pintype "passive"))
    )
    (net (code "107") (name "unconnected-(SWDIO/SWDCLK/RESET1-Pad19)") (class "Default")
      (node (ref "SWDIO/SWDCLK/RESET1") (pin "19") (pinfunction "19_19") (pintype "passive"))
    )
    (net (code "108") (name "unconnected-(U$1-ACOUSTIC_ON{slash}OFF-Pad17)") (class "Default")
      (node (ref "U$1") (pin "17") (pinfunction "ACOUSTIC_ON/OFF_17") (pintype "bidirectional"))
    )
    (net (code "109") (name "unconnected-(U$1-JETSON_ON{slash}OFF-Pad18)") (class "Default")
      (node (ref "U$1") (pin "18") (pinfunction "JETSON_ON/OFF_18") (pintype "bidirectional"))
    )
    (net (code "110") (name "unconnected-(U$1-SWITCH_2-Pad39)") (class "Default")
      (node (ref "U$1") (pin "39") (pinfunction "SWITCH_2_39") (pintype "output"))
    )
    (net (code "111") (name "unconnected-(U$1-SWITCH_3-Pad40)") (class "Default")
      (node (ref "U$1") (pin "40") (pinfunction "SWITCH_3_40") (pintype "output"))
    )
    (net (code "112") (name "unconnected-(U$1-SWITCH_4-Pad41)") (class "Default")
      (node (ref "U$1") (pin "41") (pinfunction "SWITCH_4_41") (pintype "output"))
    )
    (net (code "113") (name "unconnected-(U$1-SWITCH_5-Pad42)") (class "Default")
      (node (ref "U$1") (pin "42") (pinfunction "SWITCH_5_42") (pintype "output"))
    )
    (net (code "114") (name "unconnected-(VR1-VOUT_4-Pad4)") (class "Default")
      (node (ref "VR1") (pin "4") (pinfunction "VOUT_4_4") (pintype "output"))
    )
    (net (code "115") (name "unconnected-(W5500-DNC-Pad7)") (class "Default")
      (node (ref "W5500") (pin "7") (pinfunction "DNC_7") (pintype "bidirectional"))
    )
    (net (code "116") (name "unconnected-(W5500-DUPLED-Pad26)") (class "Default")
      (node (ref "W5500") (pin "26") (pinfunction "DUPLED_26") (pintype "output"))
    )
    (net (code "117") (name "unconnected-(W5500-PMODE0-Pad45)") (class "Default")
      (node (ref "W5500") (pin "45") (pinfunction "PMODE0_45") (pintype "input"))
    )
    (net (code "118") (name "unconnected-(W5500-PMODE1-Pad44)") (class "Default")
      (node (ref "W5500") (pin "44") (pinfunction "PMODE1_44") (pintype "input"))
    )
    (net (code "119") (name "unconnected-(W5500-PMODE2-Pad43)") (class "Default")
      (node (ref "W5500") (pin "43") (pinfunction "PMODE2_43") (pintype "input"))
    )
    (net (code "120") (name "unconnected-(W5500-RSVD2-Pad38)") (class "Default")
      (node (ref "W5500") (pin "38") (pinfunction "RSVD2_38") (pintype "input"))
    )
    (net (code "121") (name "unconnected-(W5500-RSVD3-Pad39)") (class "Default")
      (node (ref "W5500") (pin "39") (pinfunction "RSVD3_39") (pintype "input"))
    )
    (net (code "122") (name "unconnected-(W5500-RSVD4-Pad40)") (class "Default")
      (node (ref "W5500") (pin "40") (pinfunction "RSVD4_40") (pintype "input"))
    )
    (net (code "123") (name "unconnected-(W5500-RSVD5-Pad41)") (class "Default")
      (node (ref "W5500") (pin "41") (pinfunction "RSVD5_41") (pintype "input"))
    )
    (net (code "124") (name "unconnected-(W5500-RSVD6-Pad42)") (class "Default")
      (node (ref "W5500") (pin "42") (pinfunction "RSVD6_42") (pintype "input"))
    )
    (net (code "125") (name "unconnected-(W5500-SPDLED-Pad24)") (class "Default")
      (node (ref "W5500") (pin "24") (pinfunction "SPDLED_24") (pintype "output"))
    )
    (net (code "126") (name "unconnected-(W5500-VBG-Pad18)") (class "Default")
      (node (ref "W5500") (pin "18") (pinfunction "VBG_18") (pintype "output"))
    )
    (net (code "127") (name "unconnected-(W5500-~{INTN}-Pad36)") (class "Default")
      (node (ref "W5500") (pin "36") (pinfunction "~{INTN}_36") (pintype "input"))
    )
  )
)
